# PWM_Driver.net
KiCad netlist of a schematic drawn in EAGLE
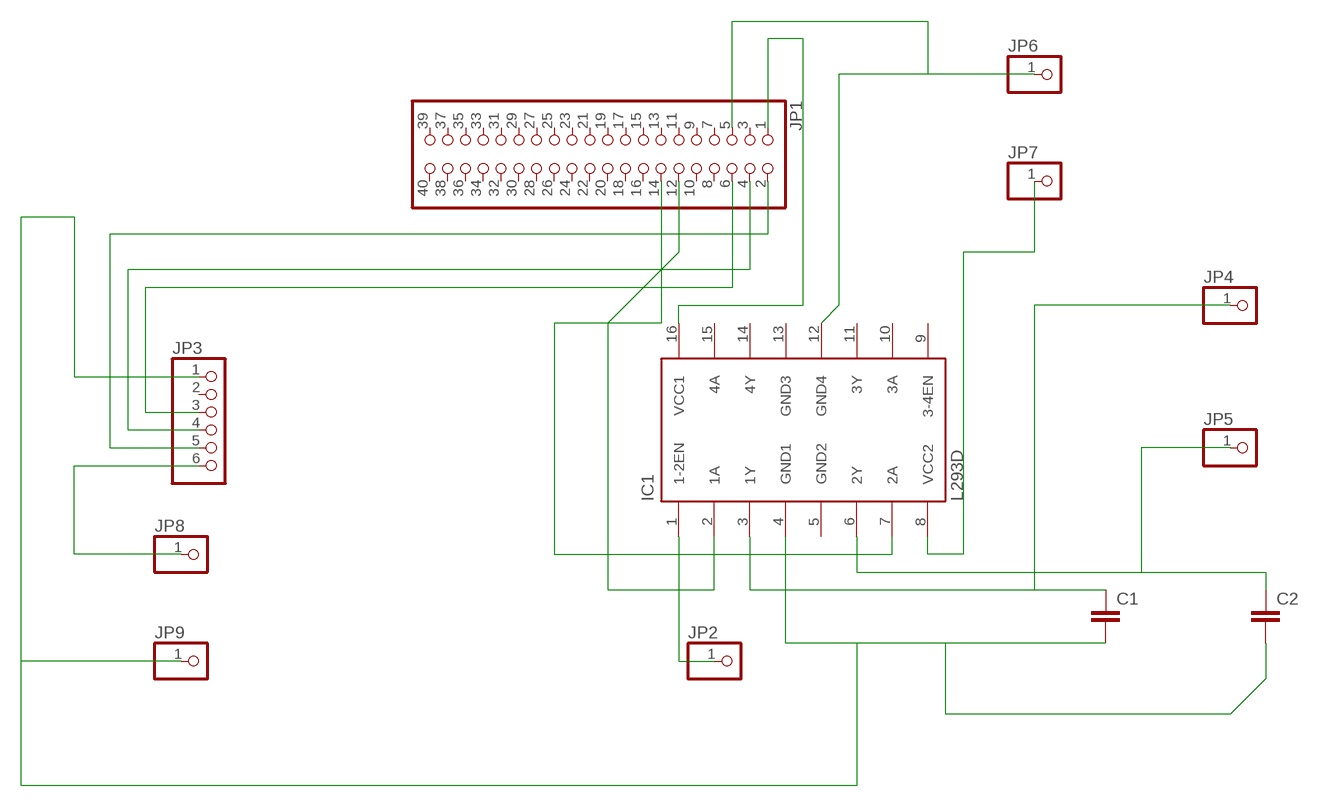
[diagram p0: schematic, sheet 1]

(export (version "E")
  (design (tool "Eeschema 10.0.6"))
  (components
    (comp (ref "C1")
      (value "C5/5")
      (footprint "eagle-import:C5B5")
      (libsource (lib "eagle-import") (part "C5/5"))
    )
    (comp (ref "C2")
      (value "C5/5")
      (footprint "eagle-import:C5B5")
      (libsource (lib "eagle-import") (part "C5/5"))
    )
    (comp (ref "IC1")
      (value "L293D")
      (footprint "eagle-import:DIL16")
      (libsource (lib "eagle-import") (part "L293D"))
    )
    (comp (ref "JP1")
      (value "PINHD-2X20")
      (footprint "eagle-import:2X20")
      (libsource (lib "eagle-import") (part "PINHD-2X20"))
    )
    (comp (ref "JP2")
      (value "PINHD-1X1")
      (footprint "eagle-import:1X01")
      (libsource (lib "eagle-import") (part "PINHD-1X1"))
    )
    (comp (ref "JP3")
      (value "PINHD-1X6")
      (footprint "eagle-import:1X06")
      (libsource (lib "eagle-import") (part "PINHD-1X6"))
    )
    (comp (ref "JP4")
      (value "PINHD-1X1")
      (footprint "eagle-import:1X01")
      (libsource (lib "eagle-import") (part "PINHD-1X1"))
    )
    (comp (ref "JP5")
      (value "PINHD-1X1")
      (footprint "eagle-import:1X01")
      (libsource (lib "eagle-import") (part "PINHD-1X1"))
    )
    (comp (ref "JP6")
      (value "PINHD-1X1")
      (footprint "eagle-import:1X01")
      (libsource (lib "eagle-import") (part "PINHD-1X1"))
    )
    (comp (ref "JP7")
      (value "PINHD-1X1")
      (footprint "eagle-import:1X01")
      (libsource (lib "eagle-import") (part "PINHD-1X1"))
    )
    (comp (ref "JP8")
      (value "PINHD-1X1")
      (footprint "eagle-import:1X01")
      (libsource (lib "eagle-import") (part "PINHD-1X1"))
    )
    (comp (ref "JP9")
      (value "PINHD-1X1")
      (footprint "eagle-import:1X01")
      (libsource (lib "eagle-import") (part "PINHD-1X1"))
    )
  )
  (nets
    (net (code "1") (name "/GND2") (class "Default")
      (node (ref "IC1") (pin "5") (pinfunction "GND2_5") (pintype "power_in"))
    )
    (net (code "2") (name "/GND3") (class "Default")
      (node (ref "IC1") (pin "13") (pinfunction "GND3_13") (pintype "power_in"))
    )
    (net (code "3") (name "Net-(IC1-1-2EN)") (class "Default")
      (node (ref "IC1") (pin "1") (pinfunction "1-2EN_1") (pintype "input"))
      (node (ref "JP2") (pin "1") (pinfunction "1_1") (pintype "passive"))
    )
    (net (code "4") (name "Net-(IC1-1A)") (class "Default")
      (node (ref "IC1") (pin "2") (pinfunction "1A_2") (pintype "input"))
      (node (ref "JP1") (pin "12") (pinfunction "12_12") (pintype "passive"))
    )
    (net (code "5") (name "Net-(IC1-1Y)") (class "Default")
      (node (ref "C1") (pin "1") (pinfunction "1_1") (pintype "passive"))
      (node (ref "IC1") (pin "3") (pinfunction "1Y_3") (pintype "output"))
      (node (ref "JP4") (pin "1") (pinfunction "1_1") (pintype "passive"))
    )
    (net (code "6") (name "Net-(IC1-2A)") (class "Default")
      (node (ref "IC1") (pin "7") (pinfunction "2A_7") (pintype "input"))
      (node (ref "JP1") (pin "14") (pinfunction "14_14") (pintype "passive"))
    )
    (net (code "7") (name "Net-(IC1-2Y)") (class "Default")
      (node (ref "C2") (pin "1") (pinfunction "1_1") (pintype "passive"))
      (node (ref "IC1") (pin "6") (pinfunction "2Y_6") (pintype "output"))
      (node (ref "JP5") (pin "1") (pinfunction "1_1") (pintype "passive"))
    )
    (net (code "8") (name "Net-(IC1-GND1)") (class "Default")
      (node (ref "C1") (pin "2") (pinfunction "2_2") (pintype "passive"))
      (node (ref "C2") (pin "2") (pinfunction "2_2") (pintype "passive"))
      (node (ref "IC1") (pin "4") (pinfunction "GND1_4") (pintype "power_in"))
      (node (ref "JP3") (pin "1") (pinfunction "1_1") (pintype "passive"))
      (node (ref "JP9") (pin "1") (pinfunction "1_1") (pintype "passive"))
    )
    (net (code "9") (name "Net-(IC1-GND4)") (class "Default")
      (node (ref "IC1") (pin "12") (pinfunction "GND4_12") (pintype "power_in"))
      (node (ref "JP1") (pin "5") (pinfunction "5_5") (pintype "passive"))
      (node (ref "JP6") (pin "1") (pinfunction "1_1") (pintype "passive"))
    )
    (net (code "10") (name "Net-(IC1-VCC1)") (class "Default")
      (node (ref "IC1") (pin "16") (pinfunction "VCC1_16") (pintype "power_in"))
      (node (ref "JP1") (pin "1") (pinfunction "1_1") (pintype "passive"))
    )
    (net (code "11") (name "Net-(IC1-VCC2)") (class "Default")
      (node (ref "IC1") (pin "8") (pinfunction "VCC2_8") (pintype "power_in"))
      (node (ref "JP7") (pin "1") (pinfunction "1_1") (pintype "passive"))
    )
    (net (code "12") (name "Net-(JP1-Pad2)") (class "Default")
      (node (ref "JP1") (pin "2") (pinfunction "2_2") (pintype "passive"))
      (node (ref "JP3") (pin "5") (pinfunction "5_5") (pintype "passive"))
    )
    (net (code "13") (name "Net-(JP1-Pad4)") (class "Default")
      (node (ref "JP1") (pin "4") (pinfunction "4_4") (pintype "passive"))
      (node (ref "JP3") (pin "4") (pinfunction "4_4") (pintype "passive"))
    )
    (net (code "14") (name "Net-(JP1-Pad6)") (class "Default")
      (node (ref "JP1") (pin "6") (pinfunction "6_6") (pintype "passive"))
      (node (ref "JP3") (pin "3") (pinfunction "3_3") (pintype "passive"))
    )
    (net (code "15") (name "Net-(JP3-Pad6)") (class "Default")
      (node (ref "JP3") (pin "6") (pinfunction "6_6") (pintype "passive"))
      (node (ref "JP8") (pin "1") (pinfunction "1_1") (pintype "passive"))
    )
    (net (code "16") (name "unconnected-(IC1-3-4EN-Pad9)") (class "Default")
      (node (ref "IC1") (pin "9") (pinfunction "3-4EN_9") (pintype "input"))
    )
    (net (code "17") (name "unconnected-(IC1-3A-Pad10)") (class "Default")
      (node (ref "IC1") (pin "10") (pinfunction "3A_10") (pintype "input"))
    )
    (net (code "18") (name "unconnected-(IC1-3Y-Pad11)") (class "Default")
      (node (ref "IC1") (pin "11") (pinfunction "3Y_11") (pintype "output"))
    )
    (net (code "19") (name "unconnected-(IC1-4A-Pad15)") (class "Default")
      (node (ref "IC1") (pin "15") (pinfunction "4A_15") (pintype "input"))
    )
    (net (code "20") (name "unconnected-(IC1-4Y-Pad14)") (class "Default")
      (node (ref "IC1") (pin "14") (pinfunction "4Y_14") (pintype "output"))
    )
    (net (code "21") (name "unconnected-(JP1-Pad3)") (class "Default")
      (node (ref "JP1") (pin "3") (pinfunction "3_3") (pintype "passive"))
    )
    (net (code "22") (name "unconnected-(JP1-Pad7)") (class "Default")
      (node (ref "JP1") (pin "7") (pinfunction "7_7") (pintype "passive"))
    )
    (net (code "23") (name "unconnected-(JP1-Pad8)") (class "Default")
      (node (ref "JP1") (pin "8") (pinfunction "8_8") (pintype "passive"))
    )
    (net (code "24") (name "unconnected-(JP1-Pad9)") (class "Default")
      (node (ref "JP1") (pin "9") (pinfunction "9_9") (pintype "passive"))
    )
    (net (code "25") (name "unconnected-(JP1-Pad10)") (class "Default")
      (node (ref "JP1") (pin "10") (pinfunction "10_10") (pintype "passive"))
    )
    (net (code "26") (name "unconnected-(JP1-Pad11)") (class "Default")
      (node (ref "JP1") (pin "11") (pinfunction "11_11") (pintype "passive"))
    )
    (net (code "27") (name "unconnected-(JP1-Pad13)") (class "Default")
      (node (ref "JP1") (pin "13") (pinfunction "13_13") (pintype "passive"))
    )
    (net (code "28") (name "unconnected-(JP1-Pad15)") (class "Default")
      (node (ref "JP1") (pin "15") (pinfunction "15_15") (pintype "passive"))
    )
    (net (code "29") (name "unconnected-(JP1-Pad16)") (class "Default")
      (node (ref "JP1") (pin "16") (pinfunction "16_16") (pintype "passive"))
    )
    (net (code "30") (name "unconnected-(JP1-Pad17)") (class "Default")
      (node (ref "JP1") (pin "17") (pinfunction "17_17") (pintype "passive"))
    )
    (net (code "31") (name "unconnected-(JP1-Pad18)") (class "Default")
      (node (ref "JP1") (pin "18") (pinfunction "18_18") (pintype "passive"))
    )
    (net (code "32") (name "unconnected-(JP1-Pad19)") (class "Default")
      (node (ref "JP1") (pin "19") (pinfunction "19_19") (pintype "passive"))
    )
    (net (code "33") (name "unconnected-(JP1-Pad20)") (class "Default")
      (node (ref "JP1") (pin "20") (pinfunction "20_20") (pintype "passive"))
    )
    (net (code "34") (name "unconnected-(JP1-Pad21)") (class "Default")
      (node (ref "JP1") (pin "21") (pinfunction "21_21") (pintype "passive"))
    )
    (net (code "35") (name "unconnected-(JP1-Pad22)") (class "Default")
      (node (ref "JP1") (pin "22") (pinfunction "22_22") (pintype "passive"))
    )
    (net (code "36") (name "unconnected-(JP1-Pad23)") (class "Default")
      (node (ref "JP1") (pin "23") (pinfunction "23_23") (pintype "passive"))
    )
    (net (code "37") (name "unconnected-(JP1-Pad24)") (class "Default")
      (node (ref "JP1") (pin "24") (pinfunction "24_24") (pintype "passive"))
    )
    (net (code "38") (name "unconnected-(JP1-Pad25)") (class "Default")
      (node (ref "JP1") (pin "25") (pinfunction "25_25") (pintype "passive"))
    )
    (net (code "39") (name "unconnected-(JP1-Pad26)") (class "Default")
      (node (ref "JP1") (pin "26") (pinfunction "26_26") (pintype "passive"))
    )
    (net (code "40") (name "unconnected-(JP1-Pad27)") (class "Default")
      (node (ref "JP1") (pin "27") (pinfunction "27_27") (pintype "passive"))
    )
    (net (code "41") (name "unconnected-(JP1-Pad28)") (class "Default")
      (node (ref "JP1") (pin "28") (pinfunction "28_28") (pintype "passive"))
    )
    (net (code "42") (name "unconnected-(JP1-Pad29)") (class "Default")
      (node (ref "JP1") (pin "29") (pinfunction "29_29") (pintype "passive"))
    )
    (net (code "43") (name "unconnected-(JP1-Pad30)") (class "Default")
      (node (ref "JP1") (pin "30") (pinfunction "30_30") (pintype "passive"))
    )
    (net (code "44") (name "unconnected-(JP1-Pad31)") (class "Default")
      (node (ref "JP1") (pin "31") (pinfunction "31_31") (pintype "passive"))
    )
    (net (code "45") (name "unconnected-(JP1-Pad32)") (class "Default")
      (node (ref "JP1") (pin "32") (pinfunction "32_32") (pintype "passive"))
    )
    (net (code "46") (name "unconnected-(JP1-Pad33)") (class "Default")
      (node (ref "JP1") (pin "33") (pinfunction "33_33") (pintype "passive"))
    )
    (net (code "47") (name "unconnected-(JP1-Pad34)") (class "Default")
      (node (ref "JP1") (pin "34") (pinfunction "34_34") (pintype "passive"))
    )
    (net (code "48") (name "unconnected-(JP1-Pad35)") (class "Default")
      (node (ref "JP1") (pin "35") (pinfunction "35_35") (pintype "passive"))
    )
    (net (code "49") (name "unconnected-(JP1-Pad36)") (class "Default")
      (node (ref "JP1") (pin "36") (pinfunction "36_36") (pintype "passive"))
    )
    (net (code "50") (name "unconnected-(JP1-Pad37)") (class "Default")
      (node (ref "JP1") (pin "37") (pinfunction "37_37") (pintype "passive"))
    )
    (net (code "51") (name "unconnected-(JP1-Pad38)") (class "Default")
      (node (ref "JP1") (pin "38") (pinfunction "38_38") (pintype "passive"))
    )
    (net (code "52") (name "unconnected-(JP1-Pad39)") (class "Default")
      (node (ref "JP1") (pin "39") (pinfunction "39_39") (pintype "passive"))
    )
    (net (code "53") (name "unconnected-(JP1-Pad40)") (class "Default")
      (node (ref "JP1") (pin "40") (pinfunction "40_40") (pintype "passive"))
    )
    (net (code "54") (name "unconnected-(JP3-Pad2)") (class "Default")
      (node (ref "JP3") (pin "2") (pinfunction "2_2") (pintype "passive"))
    )
  )
)
